# Blank_V3_1.net
KiCad netlist of a schematic drawn in EAGLE
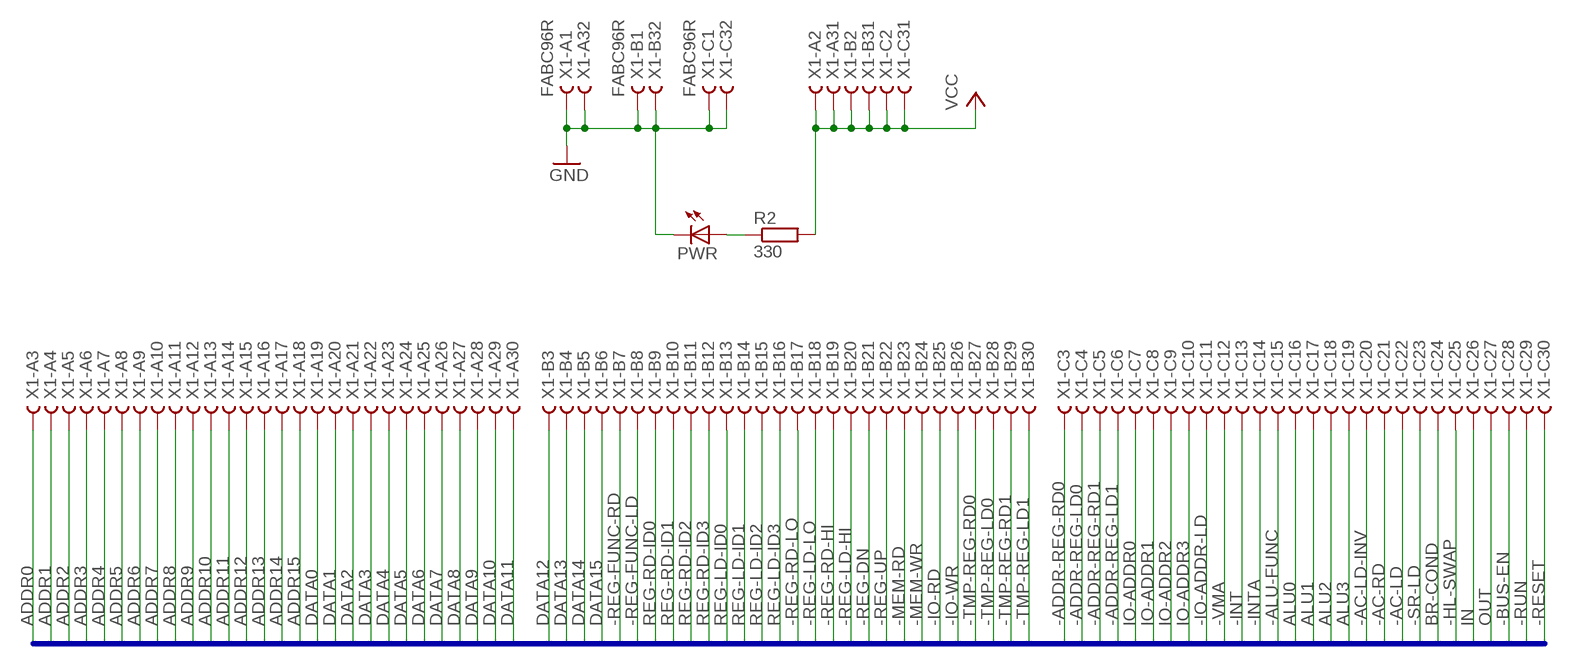
[diagram p0: schematic, sheet 1]

(export (version "E")
  (design (tool "Eeschema 10.0.6"))
  (components
    (comp (ref "PWR")
      (value "LED5MM")
      (footprint "eagle-import:LED5MM")
      (libsource (lib "eagle-import") (part "LED5MM"))
    )
    (comp (ref "R2")
      (value "330")
      (footprint "eagle-import:0207_10")
      (libsource (lib "eagle-import") (part "R0207/10"))
    )
    (comp (ref "X1")
      (value "FABC96R")
      (footprint "eagle-import:FABC96R")
      (libsource (lib "eagle-import") (part "FABC96R"))
    )
  )
  (nets
    (net (code "1") (name "/-AC-LD") (class "Default")
      (node (ref "X1") (pin "C22") (pinfunction "B_C22") (pintype "passive"))
    )
    (net (code "2") (name "/-AC-LD-INV") (class "Default")
      (node (ref "X1") (pin "C20") (pinfunction "B_C20") (pintype "passive"))
    )
    (net (code "3") (name "/-AC-RD") (class "Default")
      (node (ref "X1") (pin "C21") (pinfunction "B_C21") (pintype "passive"))
    )
    (net (code "4") (name "/-ADDR-REG-LD0") (class "Default")
      (node (ref "X1") (pin "C4") (pinfunction "B_C4") (pintype "passive"))
    )
    (net (code "5") (name "/-ADDR-REG-LD1") (class "Default")
      (node (ref "X1") (pin "C6") (pinfunction "B_C6") (pintype "passive"))
    )
    (net (code "6") (name "/-ADDR-REG-RD0") (class "Default")
      (node (ref "X1") (pin "C3") (pinfunction "B_C3") (pintype "passive"))
    )
    (net (code "7") (name "/-ADDR-REG-RD1") (class "Default")
      (node (ref "X1") (pin "C5") (pinfunction "B_C5") (pintype "passive"))
    )
    (net (code "8") (name "/-ALU-FUNC") (class "Default")
      (node (ref "X1") (pin "C15") (pinfunction "B_C15") (pintype "passive"))
    )
    (net (code "9") (name "/-BUS-EN") (class "Default")
      (node (ref "X1") (pin "C28") (pinfunction "B_C28") (pintype "passive"))
    )
    (net (code "10") (name "/-HL-SWAP") (class "Default")
      (node (ref "X1") (pin "C25") (pinfunction "B_C25") (pintype "passive"))
    )
    (net (code "11") (name "/-INT") (class "Default")
      (node (ref "X1") (pin "C13") (pinfunction "B_C13") (pintype "passive"))
    )
    (net (code "12") (name "/-INTA") (class "Default")
      (node (ref "X1") (pin "C14") (pinfunction "B_C14") (pintype "passive"))
    )
    (net (code "13") (name "/-IO-ADDR-LD") (class "Default")
      (node (ref "X1") (pin "C11") (pinfunction "B_C11") (pintype "passive"))
    )
    (net (code "14") (name "/-IO-RD") (class "Default")
      (node (ref "X1") (pin "B25") (pinfunction "B_B25") (pintype "passive"))
    )
    (net (code "15") (name "/-IO-WR") (class "Default")
      (node (ref "X1") (pin "B26") (pinfunction "B_B26") (pintype "passive"))
    )
    (net (code "16") (name "/-MEM-RD") (class "Default")
      (node (ref "X1") (pin "B23") (pinfunction "B_B23") (pintype "passive"))
    )
    (net (code "17") (name "/-MEM-WR") (class "Default")
      (node (ref "X1") (pin "B24") (pinfunction "B_B24") (pintype "passive"))
    )
    (net (code "18") (name "/-REG-DN") (class "Default")
      (node (ref "X1") (pin "B21") (pinfunction "B_B21") (pintype "passive"))
    )
    (net (code "19") (name "/-REG-FUNC-LD") (class "Default")
      (node (ref "X1") (pin "B8") (pinfunction "B_B8") (pintype "passive"))
    )
    (net (code "20") (name "/-REG-FUNC-RD") (class "Default")
      (node (ref "X1") (pin "B7") (pinfunction "B_B7") (pintype "passive"))
    )
    (net (code "21") (name "/-REG-LD-HI") (class "Default")
      (node (ref "X1") (pin "B20") (pinfunction "B_B20") (pintype "passive"))
    )
    (net (code "22") (name "/-REG-LD-LO") (class "Default")
      (node (ref "X1") (pin "B18") (pinfunction "B_B18") (pintype "passive"))
    )
    (net (code "23") (name "/-REG-RD-HI") (class "Default")
      (node (ref "X1") (pin "B19") (pinfunction "B_B19") (pintype "passive"))
    )
    (net (code "24") (name "/-REG-RD-LO") (class "Default")
      (node (ref "X1") (pin "B17") (pinfunction "B_B17") (pintype "passive"))
    )
    (net (code "25") (name "/-REG-UP") (class "Default")
      (node (ref "X1") (pin "B22") (pinfunction "B_B22") (pintype "passive"))
    )
    (net (code "26") (name "/-RESET") (class "Default")
      (node (ref "X1") (pin "C30") (pinfunction "B_C30") (pintype "passive"))
    )
    (net (code "27") (name "/-RUN") (class "Default")
      (node (ref "X1") (pin "C29") (pinfunction "B_C29") (pintype "passive"))
    )
    (net (code "28") (name "/-SR-LD") (class "Default")
      (node (ref "X1") (pin "C23") (pinfunction "B_C23") (pintype "passive"))
    )
    (net (code "29") (name "/-TMP-REG-LD0") (class "Default")
      (node (ref "X1") (pin "B28") (pinfunction "B_B28") (pintype "passive"))
    )
    (net (code "30") (name "/-TMP-REG-LD1") (class "Default")
      (node (ref "X1") (pin "B30") (pinfunction "B_B30") (pintype "passive"))
    )
    (net (code "31") (name "/-TMP-REG-RD0") (class "Default")
      (node (ref "X1") (pin "B27") (pinfunction "B_B27") (pintype "passive"))
    )
    (net (code "32") (name "/-TMP-REG-RD1") (class "Default")
      (node (ref "X1") (pin "B29") (pinfunction "B_B29") (pintype "passive"))
    )
    (net (code "33") (name "/-VMA") (class "Default")
      (node (ref "X1") (pin "C12") (pinfunction "B_C12") (pintype "passive"))
    )
    (net (code "34") (name "/ADDR0") (class "Default")
      (node (ref "X1") (pin "A3") (pinfunction "B_A3") (pintype "passive"))
    )
    (net (code "35") (name "/ADDR1") (class "Default")
      (node (ref "X1") (pin "A4") (pinfunction "B_A4") (pintype "passive"))
    )
    (net (code "36") (name "/ADDR2") (class "Default")
      (node (ref "X1") (pin "A5") (pinfunction "B_A5") (pintype "passive"))
    )
    (net (code "37") (name "/ADDR3") (class "Default")
      (node (ref "X1") (pin "A6") (pinfunction "B_A6") (pintype "passive"))
    )
    (net (code "38") (name "/ADDR4") (class "Default")
      (node (ref "X1") (pin "A7") (pinfunction "B_A7") (pintype "passive"))
    )
    (net (code "39") (name "/ADDR5") (class "Default")
      (node (ref "X1") (pin "A8") (pinfunction "B_A8") (pintype "passive"))
    )
    (net (code "40") (name "/ADDR6") (class "Default")
      (node (ref "X1") (pin "A9") (pinfunction "B_A9") (pintype "passive"))
    )
    (net (code "41") (name "/ADDR7") (class "Default")
      (node (ref "X1") (pin "A10") (pinfunction "B_A10") (pintype "passive"))
    )
    (net (code "42") (name "/ADDR8") (class "Default")
      (node (ref "X1") (pin "A11") (pinfunction "B_A11") (pintype "passive"))
    )
    (net (code "43") (name "/ADDR9") (class "Default")
      (node (ref "X1") (pin "A12") (pinfunction "B_A12") (pintype "passive"))
    )
    (net (code "44") (name "/ADDR10") (class "Default")
      (node (ref "X1") (pin "A13") (pinfunction "B_A13") (pintype "passive"))
    )
    (net (code "45") (name "/ADDR11") (class "Default")
      (node (ref "X1") (pin "A14") (pinfunction "B_A14") (pintype "passive"))
    )
    (net (code "46") (name "/ADDR12") (class "Default")
      (node (ref "X1") (pin "A15") (pinfunction "B_A15") (pintype "passive"))
    )
    (net (code "47") (name "/ADDR13") (class "Default")
      (node (ref "X1") (pin "A16") (pinfunction "B_A16") (pintype "passive"))
    )
    (net (code "48") (name "/ADDR14") (class "Default")
      (node (ref "X1") (pin "A17") (pinfunction "B_A17") (pintype "passive"))
    )
    (net (code "49") (name "/ADDR15") (class "Default")
      (node (ref "X1") (pin "A18") (pinfunction "B_A18") (pintype "passive"))
    )
    (net (code "50") (name "/ALU0") (class "Default")
      (node (ref "X1") (pin "C16") (pinfunction "B_C16") (pintype "passive"))
    )
    (net (code "51") (name "/ALU1") (class "Default")
      (node (ref "X1") (pin "C17") (pinfunction "B_C17") (pintype "passive"))
    )
    (net (code "52") (name "/ALU2") (class "Default")
      (node (ref "X1") (pin "C18") (pinfunction "B_C18") (pintype "passive"))
    )
    (net (code "53") (name "/ALU3") (class "Default")
      (node (ref "X1") (pin "C19") (pinfunction "B_C19") (pintype "passive"))
    )
    (net (code "54") (name "/BR-COND") (class "Default")
      (node (ref "X1") (pin "C24") (pinfunction "B_C24") (pintype "passive"))
    )
    (net (code "55") (name "/DATA0") (class "Default")
      (node (ref "X1") (pin "A19") (pinfunction "B_A19") (pintype "passive"))
    )
    (net (code "56") (name "/DATA1") (class "Default")
      (node (ref "X1") (pin "A20") (pinfunction "B_A20") (pintype "passive"))
    )
    (net (code "57") (name "/DATA2") (class "Default")
      (node (ref "X1") (pin "A21") (pinfunction "B_A21") (pintype "passive"))
    )
    (net (code "58") (name "/DATA3") (class "Default")
      (node (ref "X1") (pin "A22") (pinfunction "B_A22") (pintype "passive"))
    )
    (net (code "59") (name "/DATA4") (class "Default")
      (node (ref "X1") (pin "A23") (pinfunction "B_A23") (pintype "passive"))
    )
    (net (code "60") (name "/DATA5") (class "Default")
      (node (ref "X1") (pin "A24") (pinfunction "B_A24") (pintype "passive"))
    )
    (net (code "61") (name "/DATA6") (class "Default")
      (node (ref "X1") (pin "A25") (pinfunction "B_A25") (pintype "passive"))
    )
    (net (code "62") (name "/DATA7") (class "Default")
      (node (ref "X1") (pin "A26") (pinfunction "B_A26") (pintype "passive"))
    )
    (net (code "63") (name "/DATA8") (class "Default")
      (node (ref "X1") (pin "A27") (pinfunction "B_A27") (pintype "passive"))
    )
    (net (code "64") (name "/DATA9") (class "Default")
      (node (ref "X1") (pin "A28") (pinfunction "B_A28") (pintype "passive"))
    )
    (net (code "65") (name "/DATA10") (class "Default")
      (node (ref "X1") (pin "A29") (pinfunction "B_A29") (pintype "passive"))
    )
    (net (code "66") (name "/DATA11") (class "Default")
      (node (ref "X1") (pin "A30") (pinfunction "B_A30") (pintype "passive"))
    )
    (net (code "67") (name "/DATA12") (class "Default")
      (node (ref "X1") (pin "B3") (pinfunction "B_B3") (pintype "passive"))
    )
    (net (code "68") (name "/DATA13") (class "Default")
      (node (ref "X1") (pin "B4") (pinfunction "B_B4") (pintype "passive"))
    )
    (net (code "69") (name "/DATA14") (class "Default")
      (node (ref "X1") (pin "B5") (pinfunction "B_B5") (pintype "passive"))
    )
    (net (code "70") (name "/DATA15") (class "Default")
      (node (ref "X1") (pin "B6") (pinfunction "B_B6") (pintype "passive"))
    )
    (net (code "71") (name "/IN") (class "Default")
      (node (ref "X1") (pin "C26") (pinfunction "B_C26") (pintype "passive"))
    )
    (net (code "72") (name "/IO-ADDR0") (class "Default")
      (node (ref "X1") (pin "C7") (pinfunction "B_C7") (pintype "passive"))
    )
    (net (code "73") (name "/IO-ADDR1") (class "Default")
      (node (ref "X1") (pin "C8") (pinfunction "B_C8") (pintype "passive"))
    )
    (net (code "74") (name "/IO-ADDR2") (class "Default")
      (node (ref "X1") (pin "C9") (pinfunction "B_C9") (pintype "passive"))
    )
    (net (code "75") (name "/IO-ADDR3") (class "Default")
      (node (ref "X1") (pin "C10") (pinfunction "B_C10") (pintype "passive"))
    )
    (net (code "76") (name "/OUT") (class "Default")
      (node (ref "X1") (pin "C27") (pinfunction "B_C27") (pintype "passive"))
    )
    (net (code "77") (name "/REG-LD-ID0") (class "Default")
      (node (ref "X1") (pin "B13") (pinfunction "B_B13") (pintype "passive"))
    )
    (net (code "78") (name "/REG-LD-ID1") (class "Default")
      (node (ref "X1") (pin "B14") (pinfunction "B_B14") (pintype "passive"))
    )
    (net (code "79") (name "/REG-LD-ID2") (class "Default")
      (node (ref "X1") (pin "B15") (pinfunction "B_B15") (pintype "passive"))
    )
    (net (code "80") (name "/REG-LD-ID3") (class "Default")
      (node (ref "X1") (pin "B16") (pinfunction "B_B16") (pintype "passive"))
    )
    (net (code "81") (name "/REG-RD-ID0") (class "Default")
      (node (ref "X1") (pin "B9") (pinfunction "B_B9") (pintype "passive"))
    )
    (net (code "82") (name "/REG-RD-ID1") (class "Default")
      (node (ref "X1") (pin "B10") (pinfunction "B_B10") (pintype "passive"))
    )
    (net (code "83") (name "/REG-RD-ID2") (class "Default")
      (node (ref "X1") (pin "B11") (pinfunction "B_B11") (pintype "passive"))
    )
    (net (code "84") (name "/REG-RD-ID3") (class "Default")
      (node (ref "X1") (pin "B12") (pinfunction "B_B12") (pintype "passive"))
    )
    (net (code "85") (name "GND") (class "Default")
      (node (ref "PWR") (pin "K") (pinfunction "C_K") (pintype "passive"))
      (node (ref "X1") (pin "A1") (pinfunction "B_A1") (pintype "passive"))
      (node (ref "X1") (pin "A32") (pinfunction "B_A32") (pintype "passive"))
      (node (ref "X1") (pin "B1") (pinfunction "B_B1") (pintype "passive"))
      (node (ref "X1") (pin "B32") (pinfunction "B_B32") (pintype "passive"))
      (node (ref "X1") (pin "C1") (pinfunction "B_C1") (pintype "passive"))
      (node (ref "X1") (pin "C32") (pinfunction "B_C32") (pintype "passive"))
    )
    (net (code "86") (name "Net-(PWR-PadA)") (class "Default")
      (node (ref "PWR") (pin "A") (pinfunction "A_A") (pintype "passive"))
      (node (ref "R2") (pin "1") (pinfunction "1_1") (pintype "passive"))
    )
    (net (code "87") (name "VCC") (class "Default")
      (node (ref "R2") (pin "2") (pinfunction "2_2") (pintype "passive"))
      (node (ref "X1") (pin "A2") (pinfunction "B_A2") (pintype "passive"))
      (node (ref "X1") (pin "A31") (pinfunction "B_A31") (pintype "passive"))
      (node (ref "X1") (pin "B2") (pinfunction "B_B2") (pintype "passive"))
      (node (ref "X1") (pin "B31") (pinfunction "B_B31") (pintype "passive"))
      (node (ref "X1") (pin "C2") (pinfunction "B_C2") (pintype "passive"))
      (node (ref "X1") (pin "C31") (pinfunction "B_C31") (pintype "passive"))
    )
  )
)
